# EaglesPU.net
KiCad netlist of a schematic drawn in Altium Designer
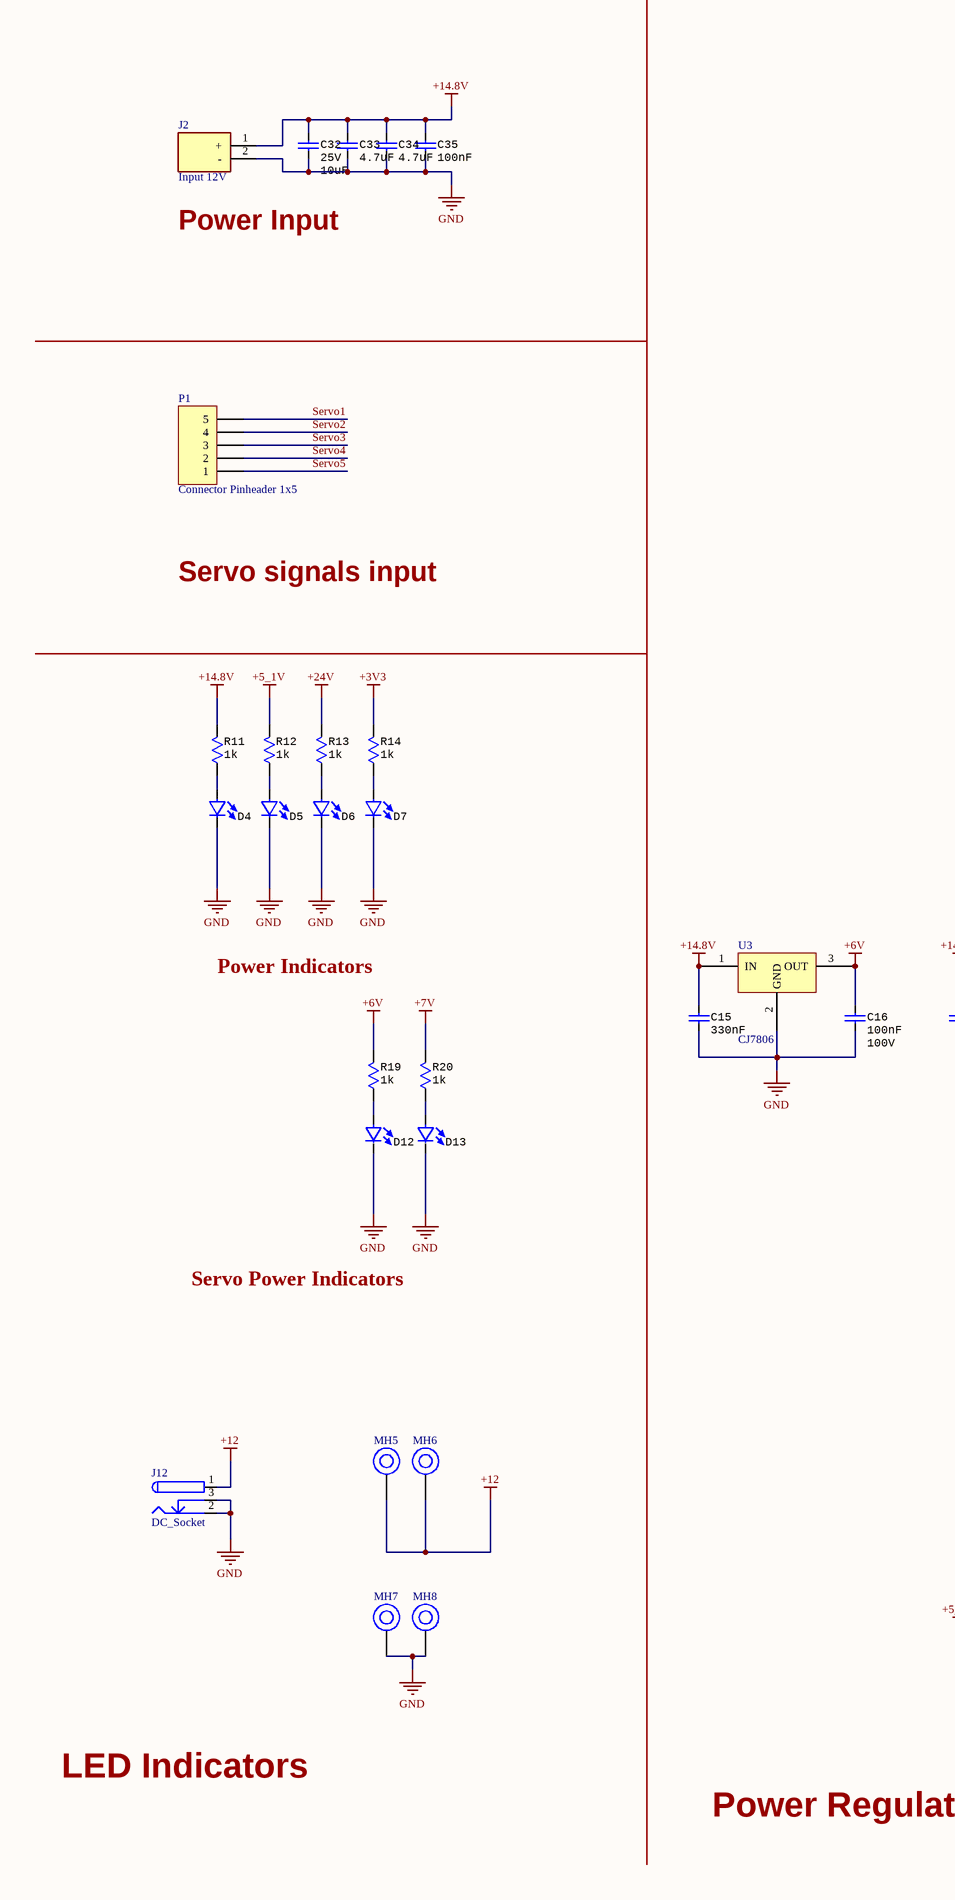
[diagram p0: EaglesPU.SchDoc, left]
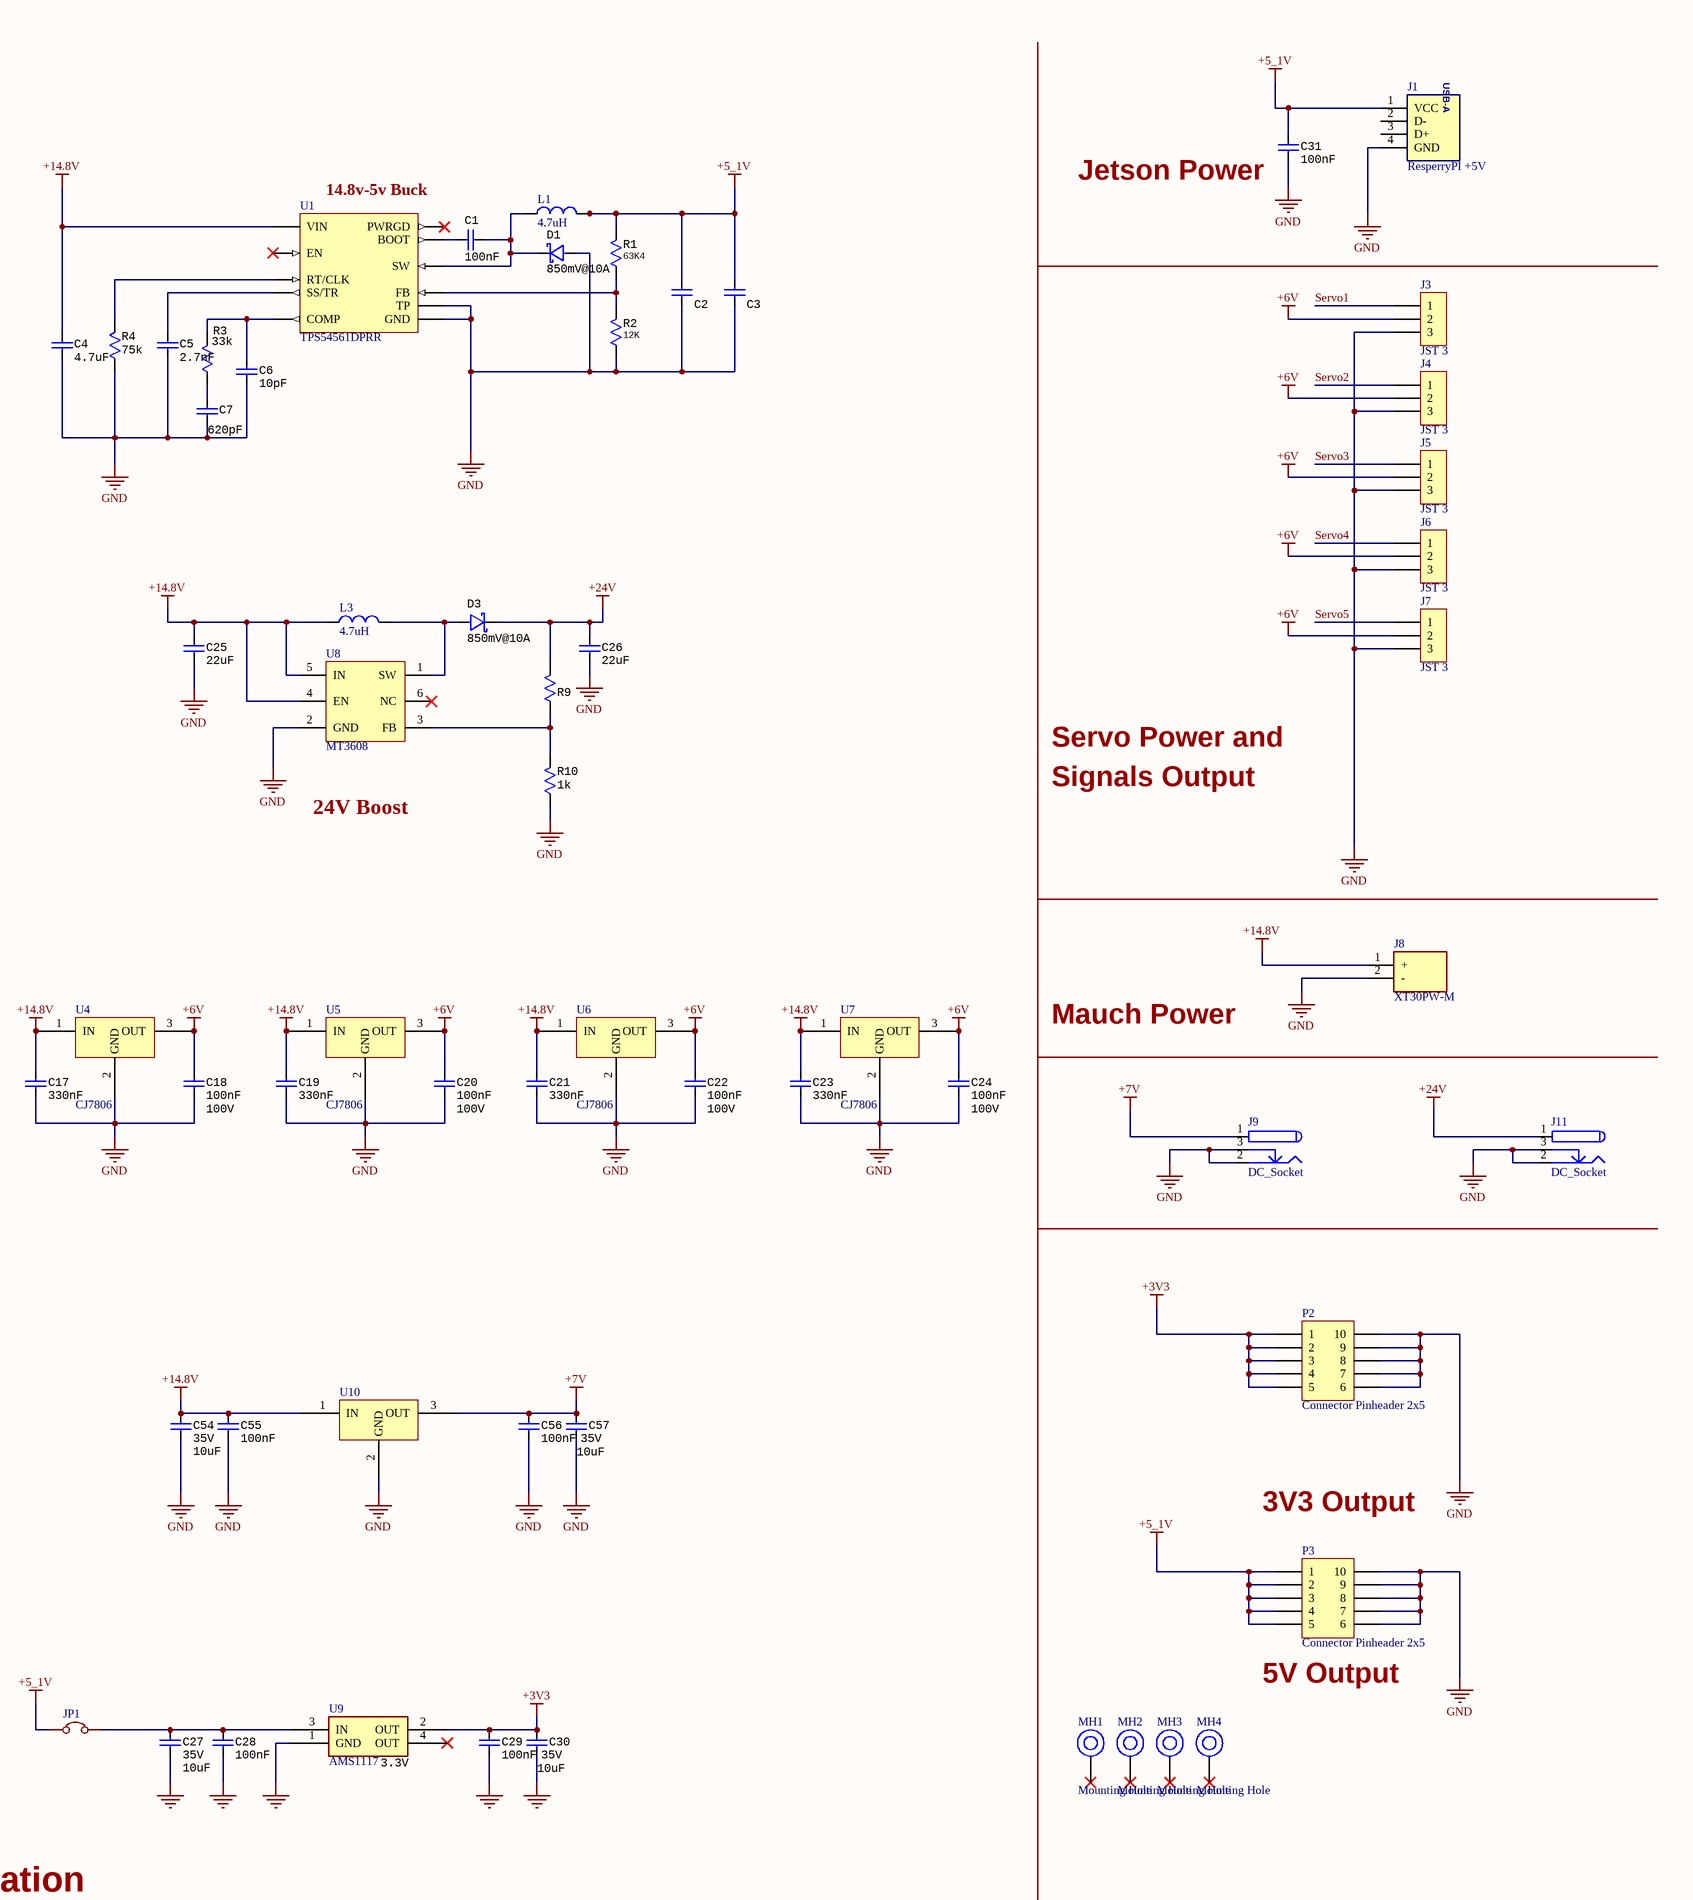
[diagram p1: EaglesPU.SchDoc, right]

(export (version "E")
  (design (tool "Eeschema 10.0.6"))
  (components
    (comp (ref "C1")
      (value "100nF")
      (footprint "CAP Ceramic SMD 0603")
      (description "0603 0.1 uF 100 V ±10% Tolerance X7R Multilayer Ceramic Capacitor")
      (fields
        (field (name "MANUFACTURER") "Yageo")
        (field (name "MANUFACTURER PART NUMBER") "CC0603KRX7R0BB104")
      )
      (libsource (lib "capacitor") (part "CAP 0603 100nF 100V"))
    )
    (comp (ref "C2")
      (value "~")
      (footprint "CAP Ceramic SMD 1206")
      (description "10V 22uF X7R ±10% 1206 Multilayer Ceramic Capacitors MLCC - SMD/SMT ROHS")
      (fields
        (field (name "MANUFACTURER") "Samsung")
        (field (name "MANUFACTURER PART NUMBER") "GRM31CR61A476ME15L")
      )
      (libsource (lib "capacitor") (part "CAP 1206 47uF 10V X5R"))
    )
    (comp (ref "C3")
      (value "~")
      (footprint "CAP Ceramic SMD 1206")
      (description "10V 22uF X7R ±10% 1206 Multilayer Ceramic Capacitors MLCC - SMD/SMT ROHS")
      (fields
        (field (name "MANUFACTURER") "Samsung")
        (field (name "MANUFACTURER PART NUMBER") "GRM31CR61A476ME15L")
      )
      (libsource (lib "capacitor") (part "CAP 1206 47uF 10V X5R"))
    )
    (comp (ref "C4")
      (value "4.7uF")
      (footprint "CAP Ceramic SMD 1206")
      (description "Cap Ceramic 4.7uF 100V X7S 10% SMD 1206 125°C Emboss T/R")
      (fields
        (field (name "MANUFACTURER PART NUMBER") "GRM31CC72A475KE11L")
        (field (name "MANUFACTURER") "Murata")
      )
      (libsource (lib "Passive") (part "CAP 1206 4.7uF 100V"))
    )
    (comp (ref "C5")
      (value "2.7nF")
      (footprint "CAP Ceramic SMD 0603")
      (description "0603 2.7 nF 50 V ±10 % Tolerance X7R SMT Multilayer Ceramic Capacitor")
      (fields
        (field (name "MANUFACTURER") "Yageo")
        (field (name "MANUFACTURER PART NUMBER") "CC0603KRX7R9BB272")
      )
      (libsource (lib "Passive") (part "CAP 0603 2.7nF 50V"))
    )
    (comp (ref "C6")
      (value "10pF")
      (footprint "CAP Ceramic SMD 0603")
      (description "Surface Mount Ceramic Multilayer Capacitor 10pF 5% C0G 50V 0603 Paper T/R")
      (fields
        (field (name "MANUFACTURER") "Yageo")
        (field (name "MANUFACTURER PART NUMBER") "CC0603JRNPO9BN100")
      )
      (libsource (lib "Passive") (part "CAP 0603 10pF 50V"))
    )
    (comp (ref "C7")
      (value "620pF")
      (footprint "CAP Ceramic SMD 0603")
      (description "Surface Mount Ceramic Multilayer Capacitor 620pF 5% C0G 50V 0603 Paper T/R")
      (fields
        (field (name "MANUFACTURER") "Yageo")
        (field (name "MANUFACTURER PART NUMBER") "CC0603JRNPO9BN621")
      )
      (libsource (lib "Passive") (part "CAP 0603 620pF 50V"))
    )
    (comp (ref "C15")
      (value "330nF")
      (footprint "CAP Ceramic SMD 0603")
      (description "Multilayer Ceramic Capacitor, 0.33 uF, 50 V, ± 10%, X7R, 0603 [1608 Metric]")
      (fields
        (field (name "MANUFACTURER") "TDK")
        (field (name "MANUFACTURER PART NUMBER") "C1608X7R1H334K080AC")
      )
      (libsource (lib "Passive") (part "CAP 0603 330nF 50V"))
    )
    (comp (ref "C16")
      (value "100nF")
      (footprint "CAP Ceramic SMD 0603")
      (description "100V 100nF X7R ±10% 0603 Multilayer Ceramic Capacitors MLCC - SMD/SMT ROHS")
      (fields
        (field (name "MANUFACTURER") "Yageo")
        (field (name "MANUFACTURER PART NUMBER") "CC0603KRX7R0BB104")
        (field (name "VOLTAGE") "100V")
      )
      (libsource (lib "capacitor") (part "CAP 0603 100nF 100V X7R 10%"))
    )
    (comp (ref "C17")
      (value "330nF")
      (footprint "CAP Ceramic SMD 0603")
      (description "Multilayer Ceramic Capacitor, 0.33 uF, 50 V, ± 10%, X7R, 0603 [1608 Metric]")
      (fields
        (field (name "MANUFACTURER") "TDK")
        (field (name "MANUFACTURER PART NUMBER") "C1608X7R1H334K080AC")
      )
      (libsource (lib "Passive") (part "CAP 0603 330nF 50V"))
    )
    (comp (ref "C18")
      (value "100nF")
      (footprint "CAP Ceramic SMD 0603")
      (description "100V 100nF X7R ±10% 0603 Multilayer Ceramic Capacitors MLCC - SMD/SMT ROHS")
      (fields
        (field (name "MANUFACTURER") "Yageo")
        (field (name "MANUFACTURER PART NUMBER") "CC0603KRX7R0BB104")
        (field (name "VOLTAGE") "100V")
      )
      (libsource (lib "capacitor") (part "CAP 0603 100nF 100V X7R 10%"))
    )
    (comp (ref "C19")
      (value "330nF")
      (footprint "CAP Ceramic SMD 0603")
      (description "Multilayer Ceramic Capacitor, 0.33 uF, 50 V, ± 10%, X7R, 0603 [1608 Metric]")
      (fields
        (field (name "MANUFACTURER") "TDK")
        (field (name "MANUFACTURER PART NUMBER") "C1608X7R1H334K080AC")
      )
      (libsource (lib "Passive") (part "CAP 0603 330nF 50V"))
    )
    (comp (ref "C20")
      (value "100nF")
      (footprint "CAP Ceramic SMD 0603")
      (description "100V 100nF X7R ±10% 0603 Multilayer Ceramic Capacitors MLCC - SMD/SMT ROHS")
      (fields
        (field (name "MANUFACTURER") "Yageo")
        (field (name "MANUFACTURER PART NUMBER") "CC0603KRX7R0BB104")
        (field (name "VOLTAGE") "100V")
      )
      (libsource (lib "capacitor") (part "CAP 0603 100nF 100V X7R 10%"))
    )
    (comp (ref "C21")
      (value "330nF")
      (footprint "CAP Ceramic SMD 0603")
      (description "Multilayer Ceramic Capacitor, 0.33 uF, 50 V, ± 10%, X7R, 0603 [1608 Metric]")
      (fields
        (field (name "MANUFACTURER") "TDK")
        (field (name "MANUFACTURER PART NUMBER") "C1608X7R1H334K080AC")
      )
      (libsource (lib "Passive") (part "CAP 0603 330nF 50V"))
    )
    (comp (ref "C22")
      (value "100nF")
      (footprint "CAP Ceramic SMD 0603")
      (description "100V 100nF X7R ±10% 0603 Multilayer Ceramic Capacitors MLCC - SMD/SMT ROHS")
      (fields
        (field (name "MANUFACTURER") "Yageo")
        (field (name "MANUFACTURER PART NUMBER") "CC0603KRX7R0BB104")
        (field (name "VOLTAGE") "100V")
      )
      (libsource (lib "capacitor") (part "CAP 0603 100nF 100V X7R 10%"))
    )
    (comp (ref "C23")
      (value "330nF")
      (footprint "CAP Ceramic SMD 0603")
      (description "Multilayer Ceramic Capacitor, 0.33 uF, 50 V, ± 10%, X7R, 0603 [1608 Metric]")
      (fields
        (field (name "MANUFACTURER") "TDK")
        (field (name "MANUFACTURER PART NUMBER") "C1608X7R1H334K080AC")
      )
      (libsource (lib "Passive") (part "CAP 0603 330nF 50V"))
    )
    (comp (ref "C24")
      (value "100nF")
      (footprint "CAP Ceramic SMD 0603")
      (description "100V 100nF X7R ±10% 0603 Multilayer Ceramic Capacitors MLCC - SMD/SMT ROHS")
      (fields
        (field (name "MANUFACTURER") "Yageo")
        (field (name "MANUFACTURER PART NUMBER") "CC0603KRX7R0BB104")
        (field (name "VOLTAGE") "100V")
      )
      (libsource (lib "capacitor") (part "CAP 0603 100nF 100V X7R 10%"))
    )
    (comp (ref "C25")
      (value "22uF")
      (footprint "CAP Ceramic SMD 0603")
      (description "6.3V 22uF X5R ±20% 0603 Multilayer Ceramic Capacitors MLCC - SMD/SMT ROHS")
      (fields
        (field (name "MANUFACTURER") "YAGEO")
        (field (name "VOLTAGE") "6.3V")
        (field (name "CAPACITANCE") "22uF")
      )
      (libsource (lib "Passive") (part "CAP 0603 22uF 6.3V"))
    )
    (comp (ref "C26")
      (value "22uF")
      (footprint "CAP Ceramic SMD 0603")
      (description "6.3V 22uF X5R ±20% 0603 Multilayer Ceramic Capacitors MLCC - SMD/SMT ROHS")
      (fields
        (field (name "MANUFACTURER") "YAGEO")
        (field (name "VOLTAGE") "6.3V")
        (field (name "CAPACITANCE") "22uF")
      )
      (libsource (lib "Passive") (part "CAP 0603 22uF 6.3V"))
    )
    (comp (ref "C27")
      (value "10uF")
      (footprint "CAP Ceramic SMD 0603")
      (description "Cap Ceramic 10uF 35V X5R 20% Pad SMD 0603 85C T/R")
      (fields
        (field (name "MANUFACTURER") "Murata")
        (field (name "MANUFACTURER PART NUMBER") "GRM188R6YA106MA73D")
        (field (name "VOLTAGE") "35V")
      )
      (libsource (lib "Passive") (part "CAP 0603 10uF 35V"))
    )
    (comp (ref "C28")
      (value "100nF")
      (footprint "CAP Ceramic SMD 0603")
      (description "0603 0.1 uF 100 V ±10% Tolerance X7R Multilayer Ceramic Capacitor")
      (fields
        (field (name "MANUFACTURER") "Yageo")
        (field (name "MANUFACTURER PART NUMBER") "AC0603KRX7R0BB104")
      )
      (libsource (lib "capacitor") (part "CAP 0603 100nF 100V"))
    )
    (comp (ref "C29")
      (value "100nF")
      (footprint "CAP Ceramic SMD 0603")
      (description "0603 0.1 uF 100 V ±10% Tolerance X7R Multilayer Ceramic Capacitor")
      (fields
        (field (name "MANUFACTURER") "Yageo")
        (field (name "MANUFACTURER PART NUMBER") "AC0603KRX7R0BB104")
      )
      (libsource (lib "capacitor") (part "CAP 0603 100nF 100V"))
    )
    (comp (ref "C30")
      (value "10uF")
      (footprint "CAP Ceramic SMD 0603")
      (description "Cap Ceramic 10uF 35V X5R 20% Pad SMD 0603 85C T/R")
      (fields
        (field (name "MANUFACTURER") "Murata")
        (field (name "MANUFACTURER PART NUMBER") "GRM188R6YA106MA73D")
        (field (name "VOLTAGE") "35V")
      )
      (libsource (lib "Passive") (part "CAP 0603 10uF 35V"))
    )
    (comp (ref "C31")
      (value "100nF")
      (footprint "CAP Ceramic SMD 0603")
      (description "0603 0.1 uF 100 V ±10% Tolerance X7R Multilayer Ceramic Capacitor")
      (fields
        (field (name "MANUFACTURER") "Yageo")
        (field (name "MANUFACTURER PART NUMBER") "CC0603KRX7R0BB104")
      )
      (libsource (lib "capacitor") (part "CAP 0603 100nF 100V"))
    )
    (comp (ref "C32")
      (value "10uF")
      (footprint "CAP Ceramic SMD 1206")
      (description "25V 10uF X7R ±10% 1206 Multilayer Ceramic Capacitors MLCC - SMD/SMT ROHS")
      (fields
        (field (name "MANUFACTURER") "Samsung Electro-Mechanics")
        (field (name "MANUFACTURER PART NUMBER") "CL31B106KAHNNNE")
        (field (name "VOLTAGE") "25V")
      )
      (libsource (lib "capacitor") (part "CAP 1206 10uF 25V X7R 10%"))
    )
    (comp (ref "C33")
      (value "4.7uF")
      (footprint "CAP Ceramic SMD 1206")
      (description "Cap Ceramic 4.7uF 100V X7S 10% SMD 1206 125°C Emboss T/R")
      (fields
        (field (name "MANUFACTURER PART NUMBER") "GRM31CC72A475KE11L")
        (field (name "MANUFACTURER") "Murata")
      )
      (libsource (lib "Passive") (part "CAP 1206 4.7uF 100V"))
    )
    (comp (ref "C34")
      (value "4.7uF")
      (footprint "CAP Ceramic SMD 1206")
      (description "Cap Ceramic 4.7uF 100V X7S 10% SMD 1206 125°C Emboss T/R")
      (fields
        (field (name "MANUFACTURER PART NUMBER") "GRM31CC72A475KE11L")
        (field (name "MANUFACTURER") "Murata")
      )
      (libsource (lib "Passive") (part "CAP 1206 4.7uF 100V"))
    )
    (comp (ref "C35")
      (value "100nF")
      (footprint "CAP Ceramic SMD 0603")
      (description "0603 0.1 uF 100 V ±10% Tolerance X7R Multilayer Ceramic Capacitor")
      (fields
        (field (name "MANUFACTURER") "Yageo")
        (field (name "MANUFACTURER PART NUMBER") "CC0603KRX7R0BB104")
      )
      (libsource (lib "capacitor") (part "CAP 0603 100nF 100V"))
    )
    (comp (ref "C54")
      (value "10uF")
      (footprint "CAP Ceramic SMD 0603")
      (description "Cap Ceramic 10uF 35V X5R 20% Pad SMD 0603 85C T/R")
      (fields
        (field (name "MANUFACTURER") "Murata")
        (field (name "MANUFACTURER PART NUMBER") "GRM188R6YA106MA73D")
        (field (name "VOLTAGE") "35V")
      )
      (libsource (lib "Passive") (part "CAP 0603 10uF 35V"))
    )
    (comp (ref "C55")
      (value "100nF")
      (footprint "CAP Ceramic SMD 0603")
      (description "0603 0.1 uF 100 V ±10% Tolerance X7R Multilayer Ceramic Capacitor")
      (fields
        (field (name "MANUFACTURER") "Yageo")
        (field (name "MANUFACTURER PART NUMBER") "AC0603KRX7R0BB104")
      )
      (libsource (lib "capacitor") (part "CAP 0603 100nF 100V"))
    )
    (comp (ref "C56")
      (value "100nF")
      (footprint "CAP Ceramic SMD 0603")
      (description "0603 0.1 uF 100 V ±10% Tolerance X7R Multilayer Ceramic Capacitor")
      (fields
        (field (name "MANUFACTURER") "Yageo")
        (field (name "MANUFACTURER PART NUMBER") "AC0603KRX7R0BB104")
      )
      (libsource (lib "capacitor") (part "CAP 0603 100nF 100V"))
    )
    (comp (ref "C57")
      (value "10uF")
      (footprint "CAP Ceramic SMD 0603")
      (description "Cap Ceramic 10uF 35V X5R 20% Pad SMD 0603 85C T/R")
      (fields
        (field (name "MANUFACTURER") "Murata")
        (field (name "MANUFACTURER PART NUMBER") "GRM188R6YA106MA73D")
        (field (name "VOLTAGE") "35V")
      )
      (libsource (lib "Passive") (part "CAP 0603 10uF 35V"))
    )
    (comp (ref "D1")
      (value "850mV@10A")
      (footprint "TO-277")
      (description "100V 750mV@10A 10A TO-277 Schottky Barrier Diodes (SBD) ROHS")
      (fields
        (field (name "MANUFACTURER") "MDD（Microdiode Electronics）")
        (field (name "MANUFACTURER PART NUMBER") "SB10100L")
      )
      (libsource (lib "Diode") (part "Schottky 100V 750mV@10A"))
    )
    (comp (ref "D3")
      (value "850mV@10A")
      (footprint "TO-277")
      (description "100V 750mV@10A 10A TO-277 Schottky Barrier Diodes (SBD) ROHS")
      (fields
        (field (name "MANUFACTURER") "MDD（Microdiode Electronics）")
        (field (name "MANUFACTURER PART NUMBER") "SB10100L")
      )
      (libsource (lib "Diode") (part "Schottky 100V 750mV@10A"))
    )
    (comp (ref "D4")
      (value "~")
      (footprint "LED SMD 0805G")
      (description "emerald 0805 Light Emitting Diodes (LED) ROHS")
      (fields
        (field (name "MANUFACTURER") "FOSHAN Nationstar Optoelectronics")
        (field (name "MANUFACTURER PART NUMBER") "NCD0805G1")
      )
      (libsource (lib "diode") (part "LED 0805 Emerald"))
    )
    (comp (ref "D5")
      (value "~")
      (footprint "LED SMD 0805G")
      (description "emerald 0805 Light Emitting Diodes (LED) ROHS")
      (fields
        (field (name "MANUFACTURER") "FOSHAN Nationstar Optoelectronics")
        (field (name "MANUFACTURER PART NUMBER") "NCD0805G1")
      )
      (libsource (lib "diode") (part "LED 0805 Emerald"))
    )
    (comp (ref "D6")
      (value "~")
      (footprint "LED SMD 0805G")
      (description "emerald 0805 Light Emitting Diodes (LED) ROHS")
      (fields
        (field (name "MANUFACTURER") "FOSHAN Nationstar Optoelectronics")
        (field (name "MANUFACTURER PART NUMBER") "NCD0805G1")
      )
      (libsource (lib "diode") (part "LED 0805 Emerald"))
    )
    (comp (ref "D7")
      (value "~")
      (footprint "LED SMD 0805G")
      (description "emerald 0805 Light Emitting Diodes (LED) ROHS")
      (fields
        (field (name "MANUFACTURER") "FOSHAN Nationstar Optoelectronics")
        (field (name "MANUFACTURER PART NUMBER") "NCD0805G1")
      )
      (libsource (lib "diode") (part "LED 0805 Emerald"))
    )
    (comp (ref "D12")
      (value "~")
      (footprint "LED SMD 0805G")
      (description "emerald 0805 Light Emitting Diodes (LED) ROHS")
      (fields
        (field (name "MANUFACTURER") "FOSHAN Nationstar Optoelectronics")
        (field (name "MANUFACTURER PART NUMBER") "NCD0805G1")
      )
      (libsource (lib "diode") (part "LED 0805 Emerald"))
    )
    (comp (ref "D13")
      (value "~")
      (footprint "LED SMD 0805G")
      (description "emerald 0805 Light Emitting Diodes (LED) ROHS")
      (fields
        (field (name "MANUFACTURER") "FOSHAN Nationstar Optoelectronics")
        (field (name "MANUFACTURER PART NUMBER") "NCD0805G1")
      )
      (libsource (lib "diode") (part "LED 0805 Emerald"))
    )
    (comp (ref "J1")
      (value "ResperryPI +5V")
      (footprint "USB-A/S_A")
      (libsource (lib "USB connectors") (part "Connector_USB-A"))
    )
    (comp (ref "J2")
      (value "Input 12V")
      (footprint "XT60PW-M")
      (description "Power Connectors ROHS")
      (fields
        (field (name "MANUFACTURER") "Changzhou Amass Elec")
        (field (name "MANUFACTURERPARTNUMBER") "XT60PW-M")
      )
      (libsource (lib "Power connectors") (part "XT60PW-M"))
    )
    (comp (ref "J3")
      (value "JST 3")
      (footprint "VH3.96-3AW")
      (description "MaleHeader 3x1")
      (libsource (lib "Signal connectors") (part "JST 3"))
    )
    (comp (ref "J4")
      (value "JST 3")
      (footprint "VH3.96-3AW")
      (description "MaleHeader 3x1")
      (libsource (lib "Signal connectors") (part "JST 3"))
    )
    (comp (ref "J5")
      (value "JST 3")
      (footprint "VH3.96-3AW")
      (description "MaleHeader 3x1")
      (libsource (lib "Signal connectors") (part "JST 3"))
    )
    (comp (ref "J6")
      (value "JST 3")
      (footprint "VH3.96-3AW")
      (description "MaleHeader 3x1")
      (libsource (lib "Signal connectors") (part "JST 3"))
    )
    (comp (ref "J7")
      (value "JST 3")
      (footprint "VH3.96-3AW")
      (description "MaleHeader 3x1")
      (libsource (lib "Signal connectors") (part "JST 3"))
    )
    (comp (ref "J8")
      (value "XT30PW-M")
      (footprint "AMASS_XT30PW-F")
      (description "Power Connectors ROHS")
      (fields (field (name "MANUFACTURER") "Changzhou Amass Elec"))
      (libsource (lib "Power connectors") (part "XT30PW-M"))
    )
    (comp (ref "J9")
      (value "DC_Socket")
      (footprint "DC-002")
      (description "CIRCULAR DC POWER CONNECTOR\r\nRated Current: 7.5A\r\nRated Volatage: 20VDC")
      (libsource (lib "Power connectors") (part "DC_Socket"))
    )
    (comp (ref "J11")
      (value "DC_Socket")
      (footprint "DC-002")
      (description "CIRCULAR DC POWER CONNECTOR\r\nRated Current: 7.5A\r\nRated Volatage: 20VDC")
      (libsource (lib "Power connectors") (part "DC_Socket"))
    )
    (comp (ref "J12")
      (value "DC_Socket")
      (footprint "DC-002")
      (description "CIRCULAR DC POWER CONNECTOR\r\nRated Current: 7.5A\r\nRated Volatage: 20VDC")
      (libsource (lib "") (part "DC_Socket_1"))
    )
    (comp (ref "JP1")
      (value "Jumper TH 2 NC")
      (footprint "Jumber TH 2 NC")
      (description "Normally closed jumper")
      (fields (field (name "MANUFACTURER") "XFCN") (field (name "MANUFACTURER PART NUMBER") "PZ254V-11-02P"))
      (libsource (lib "Bypass, Testpoint and Holes") (part "Jumper TH 2 NC"))
    )
    (comp (ref "L1")
      (value "4.7uH")
      (footprint "XLS1040")
      (description "9A 4.7uH ±20% 17mΩ 15A SMD,11.5x10x3.8mm Power Inductors ROHS")
      (fields
        (field (name "MANUFACTURER") "Cjiang")
        (field (name "MANUFACTURER PART NUMBER") "FXL1040-4R7-M")
      )
      (libsource (lib "Passive") (part "IND 0403 4.7uH 20%"))
    )
    (comp (ref "L3")
      (value "4.7uH")
      (footprint "XLS1040")
      (description "9A 4.7uH ±20% 17mΩ 15A SMD,11.5x10x3.8mm Power Inductors ROHS")
      (fields
        (field (name "MANUFACTURER") "Cjiang")
        (field (name "MANUFACTURER PART NUMBER") "FXL1040-4R7-M")
      )
      (libsource (lib "Passive") (part "IND 0403 4.7uH 20%"))
    )
    (comp (ref "MH1")
      (value "Mounting Hole")
      (footprint "Connector Mounting hole TH 3mm")
      (libsource (lib "Bypass, Testpoint and Holes") (part "Mounting Hole"))
    )
    (comp (ref "MH2")
      (value "Mounting Hole")
      (footprint "Connector Mounting hole TH 3mm")
      (libsource (lib "Bypass, Testpoint and Holes") (part "Mounting Hole"))
    )
    (comp (ref "MH3")
      (value "Mounting Hole")
      (footprint "Connector Mounting hole TH 3mm")
      (libsource (lib "Bypass, Testpoint and Holes") (part "Mounting Hole"))
    )
    (comp (ref "MH4")
      (value "Mounting Hole")
      (footprint "Connector Mounting hole TH 3mm")
      (libsource (lib "Bypass, Testpoint and Holes") (part "Mounting Hole"))
    )
    (comp (ref "MH5")
      (value "Mounting Hole")
      (footprint "Connector Mounting hole TH 1mm SOLID")
      (libsource (lib "Bypass, Testpoint and Holes") (part "Mounting Hole"))
    )
    (comp (ref "MH6")
      (value "Mounting Hole")
      (footprint "Connector Mounting hole TH 1mm SOLID")
      (libsource (lib "Bypass, Testpoint and Holes") (part "Mounting Hole"))
    )
    (comp (ref "MH7")
      (value "Mounting Hole")
      (footprint "Connector Mounting hole TH 1mm SOLID")
      (libsource (lib "Bypass, Testpoint and Holes") (part "Mounting Hole"))
    )
    (comp (ref "MH8")
      (value "Mounting Hole")
      (footprint "Connector Mounting hole TH 1mm SOLID")
      (libsource (lib "Bypass, Testpoint and Holes") (part "Mounting Hole"))
    )
    (comp (ref "P1")
      (value "Connector Pinheader 1x5")
      (footprint "Header 2.54X5")
      (description "Header_5x1")
      (libsource (lib "Signal connectors") (part "Connector Pinheader 1x5"))
    )
    (comp (ref "P2")
      (value "Connector Pinheader 2x5")
      (footprint "Header 2.54_2X5")
      (description "Header_2X5")
      (libsource (lib "Signal connectors") (part "Connector Pinheader 2x5"))
    )
    (comp (ref "P3")
      (value "Connector Pinheader 2x5")
      (footprint "Header 2.54_2X5")
      (description "Header_2X5")
      (libsource (lib "Signal connectors") (part "Connector Pinheader 2x5"))
    )
    (comp (ref "R1")
      (value "63K4")
      (footprint "RES SMD 0603")
      (fields
        (field (name "MANUFACTURER") "Yageo")
        (field (name "MANUFACTURER PART NUMBER") "AC0603FR-0763K4L")
        (field (name "TOLERANCE") "1%")
      )
      (libsource (lib "Passive") (part "RES 0603 63K4 1%"))
    )
    (comp (ref "R2")
      (value "12K")
      (footprint "RES SMD 0603")
      (fields
        (field (name "MANUFACTURER") "Yageo")
        (field (name "MANUFACTURER PART NUMBER") "RC0603FR-0712KL")
        (field (name "TOLERANCE") "1%")
      )
      (libsource (lib "Passive") (part "RES 0603 12K 1%"))
    )
    (comp (ref "R3")
      (value "33k")
      (footprint "RES SMD 0603")
      (fields
        (field (name "MANUFACTURER") "Uniroyal")
        (field (name "MANUFACTURER PART NUMBER") "0603WAF3902T5E")
      )
      (libsource (lib "Passive") (part "RES 0603 39k 1%"))
    )
    (comp (ref "R4")
      (value "75k")
      (footprint "RES SMD 0603")
      (description "Res Thick Film 0603 75K Ohm 1% 0.1W(1/10W) ±100ppm/C Pad SMD Automotive T/R")
      (fields
        (field (name "MANUFACTURER") "Panasonic")
        (field (name "MANUFACTURER PART NUMBER") "ERJ3RBD7502V")
      )
      (libsource (lib "Passive") (part "RES 0603 75k 1%"))
    )
    (comp (ref "R9")
      (value "~")
      (footprint "RES SMD 0603")
      (fields
        (field (name "MANUFACTURER") "Uniroyal")
        (field (name "MANUFACTURER PART NUMBER") "0603WAF3902T5E")
      )
      (libsource (lib "Passive") (part "RES 0603 39k 1%"))
    )
    (comp (ref "R10")
      (value "1k")
      (footprint "RES SMD 0603")
      (description "Res Thick Film 0603 1K Ohm 1% 1/10W ±100ppm/°C Molded SMD Punched Carrier T/R")
      (fields
        (field (name "MANUFACTURER") "Panasonic")
        (field (name "MANUFACTURER PART NUMBER") "ERJ3EKF1001V")
      )
      (libsource (lib "Passive") (part "RES 0603 1k 1%"))
    )
    (comp (ref "R11")
      (value "1k")
      (footprint "RES SMD 0603")
      (description "Res Thick Film 0603 1K Ohm 1% 1/10W ±100ppm/°C Molded SMD Punched Carrier T/R")
      (fields
        (field (name "MANUFACTURER") "Panasonic")
        (field (name "MANUFACTURER PART NUMBER") "ERJ3EKF1001V")
      )
      (libsource (lib "Passive") (part "RES 0603 1k 1%"))
    )
    (comp (ref "R12")
      (value "1k")
      (footprint "RES SMD 0603")
      (description "Res Thick Film 0603 1K Ohm 1% 1/10W ±100ppm/°C Molded SMD Punched Carrier T/R")
      (fields
        (field (name "MANUFACTURER") "Panasonic")
        (field (name "MANUFACTURER PART NUMBER") "ERJ3EKF1001V")
      )
      (libsource (lib "Passive") (part "RES 0603 1k 1%"))
    )
    (comp (ref "R13")
      (value "1k")
      (footprint "RES SMD 0603")
      (description "Res Thick Film 0603 1K Ohm 1% 1/10W ±100ppm/°C Molded SMD Punched Carrier T/R")
      (fields
        (field (name "MANUFACTURER") "Panasonic")
        (field (name "MANUFACTURER PART NUMBER") "ERJ3EKF1001V")
      )
      (libsource (lib "Passive") (part "RES 0603 1k 1%"))
    )
    (comp (ref "R14")
      (value "1k")
      (footprint "RES SMD 0603")
      (description "Res Thick Film 0603 1K Ohm 1% 1/10W ±100ppm/°C Molded SMD Punched Carrier T/R")
      (fields
        (field (name "MANUFACTURER") "Panasonic")
        (field (name "MANUFACTURER PART NUMBER") "ERJ3EKF1001V")
      )
      (libsource (lib "Passive") (part "RES 0603 1k 1%"))
    )
    (comp (ref "R19")
      (value "1k")
      (footprint "RES SMD 0603")
      (description "Res Thick Film 0603 1K Ohm 1% 1/10W ±100ppm/°C Molded SMD Punched Carrier T/R")
      (fields
        (field (name "MANUFACTURER") "Panasonic")
        (field (name "MANUFACTURER PART NUMBER") "ERJ3EKF1001V")
      )
      (libsource (lib "Passive") (part "RES 0603 1k 1%"))
    )
    (comp (ref "R20")
      (value "1k")
      (footprint "RES SMD 0603")
      (description "Res Thick Film 0603 1K Ohm 1% 1/10W ±100ppm/°C Molded SMD Punched Carrier T/R")
      (fields
        (field (name "MANUFACTURER") "Panasonic")
        (field (name "MANUFACTURER PART NUMBER") "ERJ3EKF1001V")
      )
      (libsource (lib "Passive") (part "RES 0603 1k 1%"))
    )
    (comp (ref "U1")
      (value "TPS54561DPRR")
      (footprint "TPS54561DPRR")
      (description "4.5V to 60V Input 5A Step-Down DC-DC Converter With Soft-Start and Eco-mode 10-WSON -40 to 125")
      (fields (field (name "MANUFACTURER") "Texas Instruments"))
      (libsource (lib "PMIC") (part "TPS54561DPRR"))
    )
    (comp (ref "U3")
      (value "CJ7806")
      (footprint "REGULATOR TO-252(4R)-2L")
      (fields (field (name "MANUFACTURER") "JIANGSU CHANGJIANG ELECTRONICS TECHNOLOGY CO., LTD"))
      (libsource (lib "PMIC") (part "CJ7806"))
    )
    (comp (ref "U4")
      (value "CJ7806")
      (footprint "REGULATOR TO-252(4R)-2L")
      (fields (field (name "MANUFACTURER") "JIANGSU CHANGJIANG ELECTRONICS TECHNOLOGY CO., LTD"))
      (libsource (lib "PMIC") (part "CJ7806"))
    )
    (comp (ref "U5")
      (value "CJ7806")
      (footprint "REGULATOR TO-252(4R)-2L")
      (fields (field (name "MANUFACTURER") "JIANGSU CHANGJIANG ELECTRONICS TECHNOLOGY CO., LTD"))
      (libsource (lib "PMIC") (part "CJ7806"))
    )
    (comp (ref "U6")
      (value "CJ7806")
      (footprint "REGULATOR TO-252(4R)-2L")
      (fields (field (name "MANUFACTURER") "JIANGSU CHANGJIANG ELECTRONICS TECHNOLOGY CO., LTD"))
      (libsource (lib "PMIC") (part "CJ7806"))
    )
    (comp (ref "U7")
      (value "CJ7806")
      (footprint "REGULATOR TO-252(4R)-2L")
      (fields (field (name "MANUFACTURER") "JIANGSU CHANGJIANG ELECTRONICS TECHNOLOGY CO., LTD"))
      (libsource (lib "PMIC") (part "CJ7806"))
    )
    (comp (ref "U8")
      (value "MT3608")
      (footprint "MT3608")
      (description "boost converterType 28V 2V~24V SOT-23-6 DC-DC Converters ROHS")
      (fields (field (name "MANUFACTURER") "XI'AN Aerosemi Tech"))
      (libsource (lib "PMIC") (part "MT3608"))
    )
    (comp (ref "U9")
      (value "AMS1117")
      (footprint "Linear reagulator SMD AMS1117 - duplicate")
      (fields
        (field (name "MANUFACTURER") "Advanced Monolithic Systems")
        (field (name "VOLTAGE OUTPUT") "3.3V")
      )
      (libsource (lib "Linear regulator") (part "AMS1117"))
    )
    (comp (ref "U10")
      (value "BA7807FP-E2")
      (footprint "BA7807FP-E2")
      (description "1A 69dB@(120Hz) Fixed 7V Positive electrode 22V TO-252-3 Linear Voltage Regulators (LDO) ROHS")
      (fields (field (name "MANUFACTURER") "ROHM Semicon"))
      (libsource (lib "PMIC") (part "BA7807FP-E2"))
    )
  )
  (nets
    (net (code "1") (name "+3V3") (class "Default")
      (node (ref "C29") (pin "1") (pinfunction "1_1") (pintype "passive"))
      (node (ref "C30") (pin "1") (pinfunction "1_1") (pintype "passive"))
      (node (ref "P2") (pin "1") (pinfunction "1_1") (pintype "power_in"))
      (node (ref "P2") (pin "2") (pinfunction "2_2") (pintype "power_in"))
      (node (ref "P2") (pin "3") (pinfunction "3_3") (pintype "power_in"))
      (node (ref "P2") (pin "4") (pinfunction "4_4") (pintype "power_in"))
      (node (ref "P2") (pin "5") (pinfunction "5_5") (pintype "power_in"))
      (node (ref "R14") (pin "2") (pinfunction "2_2") (pintype "passive"))
      (node (ref "U9") (pin "2") (pinfunction "OUT_2") (pintype "passive"))
    )
    (net (code "2") (name "+5_1V") (class "Default")
      (node (ref "C2") (pin "1") (pinfunction "1_1") (pintype "passive"))
      (node (ref "C3") (pin "1") (pinfunction "1_1") (pintype "passive"))
      (node (ref "C31") (pin "1") (pinfunction "1_1") (pintype "passive"))
      (node (ref "J1") (pin "1") (pinfunction "VCC_1") (pintype "passive"))
      (node (ref "JP1") (pin "1") (pinfunction "1_1") (pintype "passive"))
      (node (ref "L1") (pin "1") (pinfunction "1_1") (pintype "passive"))
      (node (ref "P3") (pin "1") (pinfunction "1_1") (pintype "power_in"))
      (node (ref "P3") (pin "2") (pinfunction "2_2") (pintype "power_in"))
      (node (ref "P3") (pin "3") (pinfunction "3_3") (pintype "power_in"))
      (node (ref "P3") (pin "4") (pinfunction "4_4") (pintype "power_in"))
      (node (ref "P3") (pin "5") (pinfunction "5_5") (pintype "power_in"))
      (node (ref "R1") (pin "2") (pinfunction "2_2") (pintype "passive"))
      (node (ref "R12") (pin "2") (pinfunction "2_2") (pintype "passive"))
    )
    (net (code "3") (name "+6V") (class "Default")
      (node (ref "C16") (pin "1") (pinfunction "1_1") (pintype "passive"))
      (node (ref "C18") (pin "1") (pinfunction "1_1") (pintype "passive"))
      (node (ref "C20") (pin "1") (pinfunction "1_1") (pintype "passive"))
      (node (ref "C22") (pin "1") (pinfunction "1_1") (pintype "passive"))
      (node (ref "C24") (pin "1") (pinfunction "1_1") (pintype "passive"))
      (node (ref "J3") (pin "2") (pinfunction "2_2") (pintype "passive"))
      (node (ref "J4") (pin "2") (pinfunction "2_2") (pintype "passive"))
      (node (ref "J5") (pin "2") (pinfunction "2_2") (pintype "passive"))
      (node (ref "J6") (pin "2") (pinfunction "2_2") (pintype "passive"))
      (node (ref "J7") (pin "2") (pinfunction "2_2") (pintype "passive"))
      (node (ref "R19") (pin "2") (pinfunction "2_2") (pintype "passive"))
      (node (ref "U3") (pin "3") (pinfunction "OUT_3") (pintype "passive"))
      (node (ref "U4") (pin "3") (pinfunction "OUT_3") (pintype "passive"))
      (node (ref "U5") (pin "3") (pinfunction "OUT_3") (pintype "passive"))
      (node (ref "U6") (pin "3") (pinfunction "OUT_3") (pintype "passive"))
      (node (ref "U7") (pin "3") (pinfunction "OUT_3") (pintype "passive"))
    )
    (net (code "4") (name "+7V") (class "Default")
      (node (ref "C56") (pin "1") (pinfunction "1_1") (pintype "passive"))
      (node (ref "C57") (pin "1") (pinfunction "1_1") (pintype "passive"))
      (node (ref "J9") (pin "1") (pinfunction "1_1") (pintype "power_in"))
      (node (ref "R20") (pin "2") (pinfunction "2_2") (pintype "passive"))
      (node (ref "U10") (pin "3") (pinfunction "OUT_3") (pintype "passive"))
    )
    (net (code "5") (name "+12") (class "Default")
      (node (ref "J12") (pin "1") (pinfunction "1_1") (pintype "power_in"))
      (node (ref "MH5") (pin "1") (pinfunction "1_1") (pintype "passive"))
      (node (ref "MH6") (pin "1") (pinfunction "1_1") (pintype "passive"))
    )
    (net (code "6") (name "+14.8V") (class "Default")
      (node (ref "C15") (pin "1") (pinfunction "1_1") (pintype "passive"))
      (node (ref "C17") (pin "1") (pinfunction "1_1") (pintype "passive"))
      (node (ref "C19") (pin "1") (pinfunction "1_1") (pintype "passive"))
      (node (ref "C21") (pin "1") (pinfunction "1_1") (pintype "passive"))
      (node (ref "C23") (pin "1") (pinfunction "1_1") (pintype "passive"))
      (node (ref "C25") (pin "1") (pinfunction "1_1") (pintype "passive"))
      (node (ref "C32") (pin "1") (pinfunction "1_1") (pintype "passive"))
      (node (ref "C33") (pin "1") (pinfunction "1_1") (pintype "passive"))
      (node (ref "C34") (pin "1") (pinfunction "1_1") (pintype "passive"))
      (node (ref "C35") (pin "1") (pinfunction "1_1") (pintype "passive"))
      (node (ref "C4") (pin "1") (pinfunction "1_1") (pintype "passive"))
      (node (ref "C54") (pin "1") (pinfunction "1_1") (pintype "passive"))
      (node (ref "C55") (pin "1") (pinfunction "1_1") (pintype "passive"))
      (node (ref "J2") (pin "1") (pinfunction "+_1") (pintype "passive"))
      (node (ref "J8") (pin "1") (pinfunction "+_1") (pintype "passive"))
      (node (ref "L3") (pin "2") (pinfunction "2_2") (pintype "passive"))
      (node (ref "R11") (pin "2") (pinfunction "2_2") (pintype "passive"))
      (node (ref "U1") (pin "2") (pinfunction "VIN_2") (pintype "power_in"))
      (node (ref "U10") (pin "1") (pinfunction "IN_1") (pintype "passive"))
      (node (ref "U3") (pin "1") (pinfunction "IN_1") (pintype "passive"))
      (node (ref "U4") (pin "1") (pinfunction "IN_1") (pintype "passive"))
      (node (ref "U5") (pin "1") (pinfunction "IN_1") (pintype "passive"))
      (node (ref "U6") (pin "1") (pinfunction "IN_1") (pintype "passive"))
      (node (ref "U7") (pin "1") (pinfunction "IN_1") (pintype "passive"))
      (node (ref "U8") (pin "4") (pinfunction "EN_4") (pintype "power_in"))
      (node (ref "U8") (pin "5") (pinfunction "IN_5") (pintype "power_in"))
    )
    (net (code "7") (name "+24V") (class "Default")
      (node (ref "C26") (pin "1") (pinfunction "1_1") (pintype "passive"))
      (node (ref "D3") (pin "C") (pinfunction "C_C") (pintype "passive"))
      (node (ref "J11") (pin "1") (pinfunction "1_1") (pintype "power_in"))
      (node (ref "R13") (pin "2") (pinfunction "2_2") (pintype "passive"))
      (node (ref "R9") (pin "2") (pinfunction "2_2") (pintype "passive"))
    )
    (net (code "8") (name "/Servo1") (class "Default")
      (node (ref "J3") (pin "1") (pinfunction "1_1") (pintype "passive"))
      (node (ref "P1") (pin "5") (pinfunction "5_5") (pintype "passive"))
    )
    (net (code "9") (name "/Servo2") (class "Default")
      (node (ref "J4") (pin "1") (pinfunction "1_1") (pintype "passive"))
      (node (ref "P1") (pin "4") (pinfunction "4_4") (pintype "passive"))
    )
    (net (code "10") (name "/Servo3") (class "Default")
      (node (ref "J5") (pin "1") (pinfunction "1_1") (pintype "passive"))
      (node (ref "P1") (pin "3") (pinfunction "3_3") (pintype "passive"))
    )
    (net (code "11") (name "/Servo4") (class "Default")
      (node (ref "J6") (pin "1") (pinfunction "1_1") (pintype "passive"))
      (node (ref "P1") (pin "2") (pinfunction "2_2") (pintype "passive"))
    )
    (net (code "12") (name "/Servo5") (class "Default")
      (node (ref "J7") (pin "1") (pinfunction "1_1") (pintype "passive"))
      (node (ref "P1") (pin "1") (pinfunction "1_1") (pintype "passive"))
    )
    (net (code "13") (name "GND") (class "Default")
      (node (ref "C15") (pin "2") (pinfunction "2_2") (pintype "passive"))
      (node (ref "C16") (pin "2") (pinfunction "2_2") (pintype "passive"))
      (node (ref "C17") (pin "2") (pinfunction "2_2") (pintype "passive"))
      (node (ref "C18") (pin "2") (pinfunction "2_2") (pintype "passive"))
      (node (ref "C19") (pin "2") (pinfunction "2_2") (pintype "passive"))
      (node (ref "C2") (pin "2") (pinfunction "2_2") (pintype "passive"))
      (node (ref "C20") (pin "2") (pinfunction "2_2") (pintype "passive"))
      (node (ref "C21") (pin "2") (pinfunction "2_2") (pintype "passive"))
      (node (ref "C22") (pin "2") (pinfunction "2_2") (pintype "passive"))
      (node (ref "C23") (pin "2") (pinfunction "2_2") (pintype "passive"))
      (node (ref "C24") (pin "2") (pinfunction "2_2") (pintype "passive"))
      (node (ref "C25") (pin "2") (pinfunction "2_2") (pintype "passive"))
      (node (ref "C26") (pin "2") (pinfunction "2_2") (pintype "passive"))
      (node (ref "C27") (pin "2") (pinfunction "2_2") (pintype "passive"))
      (node (ref "C28") (pin "2") (pinfunction "2_2") (pintype "passive"))
      (node (ref "C29") (pin "2") (pinfunction "2_2") (pintype "passive"))
      (node (ref "C3") (pin "2") (pinfunction "2_2") (pintype "passive"))
      (node (ref "C30") (pin "2") (pinfunction "2_2") (pintype "passive"))
      (node (ref "C31") (pin "2") (pinfunction "2_2") (pintype "passive"))
      (node (ref "C32") (pin "2") (pinfunction "2_2") (pintype "passive"))
      (node (ref "C33") (pin "2") (pinfunction "2_2") (pintype "passive"))
      (node (ref "C34") (pin "2") (pinfunction "2_2") (pintype "passive"))
      (node (ref "C35") (pin "2") (pinfunction "2_2") (pintype "passive"))
      (node (ref "C4") (pin "2") (pinfunction "2_2") (pintype "passive"))
      (node (ref "C5") (pin "2") (pinfunction "2_2") (pintype "passive"))
      (node (ref "C54") (pin "2") (pinfunction "2_2") (pintype "passive"))
      (node (ref "C55") (pin "2") (pinfunction "2_2") (pintype "passive"))
      (node (ref "C56") (pin "2") (pinfunction "2_2") (pintype "passive"))
      (node (ref "C57") (pin "2") (pinfunction "2_2") (pintype "passive"))
      (node (ref "C6") (pin "2") (pinfunction "2_2") (pintype "passive"))
      (node (ref "C7") (pin "2") (pinfunction "2_2") (pintype "passive"))
      (node (ref "D1") (pin "A") (pinfunction "A_A") (pintype "passive"))
      (node (ref "D12") (pin "2") (pinfunction "2_2") (pintype "passive"))
      (node (ref "D13") (pin "2") (pinfunction "2_2") (pintype "passive"))
      (node (ref "D4") (pin "2") (pinfunction "2_2") (pintype "passive"))
      (node (ref "D5") (pin "2") (pinfunction "2_2") (pintype "passive"))
      (node (ref "D6") (pin "2") (pinfunction "2_2") (pintype "passive"))
      (node (ref "D7") (pin "2") (pinfunction "2_2") (pintype "passive"))
      (node (ref "J1") (pin "4") (pinfunction "GND_4") (pintype "passive"))
      (node (ref "J11") (pin "2") (pinfunction "2_2") (pintype "power_in"))
      (node (ref "J11") (pin "3") (pinfunction "3_3") (pintype "power_in"))
      (node (ref "J12") (pin "2") (pinfunction "2_2") (pintype "power_in"))
      (node (ref "J12") (pin "3") (pinfunction "3_3") (pintype "power_in"))
      (node (ref "J2") (pin "2") (pinfunction "-_2") (pintype "passive"))
      (node (ref "J3") (pin "3") (pinfunction "3_3") (pintype "passive"))
      (node (ref "J4") (pin "3") (pinfunction "3_3") (pintype "passive"))
      (node (ref "J5") (pin "3") (pinfunction "3_3") (pintype "passive"))
      (node (ref "J6") (pin "3") (pinfunction "3_3") (pintype "passive"))
      (node (ref "J7") (pin "3") (pinfunction "3_3") (pintype "passive"))
      (node (ref "J8") (pin "2") (pinfunction "-_2") (pintype "passive"))
      (node (ref "J9") (pin "2") (pinfunction "2_2") (pintype "power_in"))
      (node (ref "J9") (pin "3") (pinfunction "3_3") (pintype "power_in"))
      (node (ref "MH7") (pin "1") (pinfunction "1_1") (pintype "passive"))
      (node (ref "MH8") (pin "1") (pinfunction "1_1") (pintype "passive"))
      (node (ref "P2") (pin "10") (pinfunction "10_10") (pintype "power_in"))
      (node (ref "P2") (pin "6") (pinfunction "6_6") (pintype "power_in"))
      (node (ref "P2") (pin "7") (pinfunction "7_7") (pintype "power_in"))
      (node (ref "P2") (pin "8") (pinfunction "8_8") (pintype "power_in"))
      (node (ref "P2") (pin "9") (pinfunction "9_9") (pintype "power_in"))
      (node (ref "P3") (pin "10") (pinfunction "10_10") (pintype "power_in"))
      (node (ref "P3") (pin "6") (pinfunction "6_6") (pintype "power_in"))
      (node (ref "P3") (pin "7") (pinfunction "7_7") (pintype "power_in"))
      (node (ref "P3") (pin "8") (pinfunction "8_8") (pintype "power_in"))
      (node (ref "P3") (pin "9") (pinfunction "9_9") (pintype "power_in"))
      (node (ref "R10") (pin "1") (pinfunction "1_1") (pintype "passive"))
      (node (ref "R2") (pin "1") (pinfunction "1_1") (pintype "passive"))
      (node (ref "R4") (pin "1") (pinfunction "1_1") (pintype "passive"))
      (node (ref "U1") (pin "11") (pinfunction "TP_11") (pintype "power_in"))
      (node (ref "U1") (pin "8") (pinfunction "GND_8") (pintype "power_in"))
      (node (ref "U10") (pin "2") (pinfunction "GND_2") (pintype "passive"))
      (node (ref "U3") (pin "2") (pinfunction "GND_2") (pintype "passive"))
      (node (ref "U4") (pin "2") (pinfunction "GND_2") (pintype "passive"))
      (node (ref "U5") (pin "2") (pinfunction "GND_2") (pintype "passive"))
      (node (ref "U6") (pin "2") (pinfunction "GND_2") (pintype "passive"))
      (node (ref "U7") (pin "2") (pinfunction "GND_2") (pintype "passive"))
      (node (ref "U8") (pin "2") (pinfunction "GND_2") (pintype "power_in"))
      (node (ref "U9") (pin "1") (pinfunction "GND_1") (pintype "passive"))
    )
    (net (code "14") (name "Net-(C7-Pad1)") (class "Default")
      (node (ref "C7") (pin "1") (pinfunction "1_1") (pintype "passive"))
      (node (ref "R3") (pin "1") (pinfunction "1_1") (pintype "passive"))
    )
    (net (code "15") (name "Net-(D4-Pad1)") (class "Default")
      (node (ref "D4") (pin "1") (pinfunction "1_1") (pintype "passive"))
      (node (ref "R11") (pin "1") (pinfunction "1_1") (pintype "passive"))
    )
    (net (code "16") (name "Net-(D5-Pad1)") (class "Default")
      (node (ref "D5") (pin "1") (pinfunction "1_1") (pintype "passive"))
      (node (ref "R12") (pin "1") (pinfunction "1_1") (pintype "passive"))
    )
    (net (code "17") (name "Net-(D6-Pad1)") (class "Default")
      (node (ref "D6") (pin "1") (pinfunction "1_1") (pintype "passive"))
      (node (ref "R13") (pin "1") (pinfunction "1_1") (pintype "passive"))
    )
    (net (code "18") (name "Net-(D7-Pad1)") (class "Default")
      (node (ref "D7") (pin "1") (pinfunction "1_1") (pintype "passive"))
      (node (ref "R14") (pin "1") (pinfunction "1_1") (pintype "passive"))
    )
    (net (code "19") (name "Net-(D12-Pad1)") (class "Default")
      (node (ref "D12") (pin "1") (pinfunction "1_1") (pintype "passive"))
      (node (ref "R19") (pin "1") (pinfunction "1_1") (pintype "passive"))
    )
    (net (code "20") (name "Net-(D13-Pad1)") (class "Default")
      (node (ref "D13") (pin "1") (pinfunction "1_1") (pintype "passive"))
      (node (ref "R20") (pin "1") (pinfunction "1_1") (pintype "passive"))
    )
    (net (code "21") (name "Net-(U1-BOOT)") (class "Default")
      (node (ref "C1") (pin "1") (pinfunction "1_1") (pintype "passive"))
      (node (ref "U1") (pin "1") (pinfunction "BOOT_1") (pintype "output"))
    )
    (net (code "22") (name "Net-(U1-COMP)") (class "Default")
      (node (ref "C6") (pin "1") (pinfunction "1_1") (pintype "passive"))
      (node (ref "R3") (pin "2") (pinfunction "2_2") (pintype "passive"))
      (node (ref "U1") (pin "7") (pinfunction "COMP_7") (pintype "output"))
    )
    (net (code "23") (name "Net-(U1-FB)") (class "Default")
      (node (ref "R1") (pin "1") (pinfunction "1_1") (pintype "passive"))
      (node (ref "R2") (pin "2") (pinfunction "2_2") (pintype "passive"))
      (node (ref "U1") (pin "6") (pinfunction "FB_6") (pintype "input"))
    )
    (net (code "24") (name "Net-(U1-RT{slash}CLK)") (class "Default")
      (node (ref "R4") (pin "2") (pinfunction "2_2") (pintype "passive"))
      (node (ref "U1") (pin "5") (pinfunction "RT/CLK_5") (pintype "input"))
    )
    (net (code "25") (name "Net-(U1-SS{slash}TR)") (class "Default")
      (node (ref "C5") (pin "1") (pinfunction "1_1") (pintype "passive"))
      (node (ref "U1") (pin "4") (pinfunction "SS/TR_4") (pintype "output"))
    )
    (net (code "26") (name "Net-(U1-SW)") (class "Default")
      (node (ref "C1") (pin "2") (pinfunction "2_2") (pintype "passive"))
      (node (ref "D1") (pin "C") (pinfunction "C_C") (pintype "passive"))
      (node (ref "L1") (pin "2") (pinfunction "2_2") (pintype "passive"))
      (node (ref "U1") (pin "9") (pinfunction "SW_9") (pintype "input"))
    )
    (net (code "27") (name "Net-(U8-FB)") (class "Default")
      (node (ref "R10") (pin "2") (pinfunction "2_2") (pintype "passive"))
      (node (ref "R9") (pin "1") (pinfunction "1_1") (pintype "passive"))
      (node (ref "U8") (pin "3") (pinfunction "FB_3") (pintype "power_in"))
    )
    (net (code "28") (name "Net-(U8-SW)") (class "Default")
      (node (ref "D3") (pin "A") (pinfunction "A_A") (pintype "passive"))
      (node (ref "L3") (pin "1") (pinfunction "1_1") (pintype "passive"))
      (node (ref "U8") (pin "1") (pinfunction "SW_1") (pintype "power_in"))
    )
    (net (code "29") (name "Net-(U9-IN)") (class "Default")
      (node (ref "C27") (pin "1") (pinfunction "1_1") (pintype "passive"))
      (node (ref "C28") (pin "1") (pinfunction "1_1") (pintype "passive"))
      (node (ref "JP1") (pin "2") (pinfunction "2_2") (pintype "passive"))
      (node (ref "U9") (pin "3") (pinfunction "IN_3") (pintype "passive"))
    )
    (net (code "30") (name "unconnected-(J1-D+-Pad3)") (class "Default")
      (node (ref "J1") (pin "3") (pinfunction "D+_3") (pintype "passive"))
    )
    (net (code "31") (name "unconnected-(J1-D--Pad2)") (class "Default")
      (node (ref "J1") (pin "2") (pinfunction "D-_2") (pintype "passive"))
    )
    (net (code "32") (name "unconnected-(MH1-Pad1)") (class "Default")
      (node (ref "MH1") (pin "1") (pinfunction "1_1") (pintype "passive+no_connect"))
    )
    (net (code "33") (name "unconnected-(MH2-Pad1)") (class "Default")
      (node (ref "MH2") (pin "1") (pinfunction "1_1") (pintype "passive+no_connect"))
    )
    (net (code "34") (name "unconnected-(MH3-Pad1)") (class "Default")
      (node (ref "MH3") (pin "1") (pinfunction "1_1") (pintype "passive+no_connect"))
    )
    (net (code "35") (name "unconnected-(MH4-Pad1)") (class "Default")
      (node (ref "MH4") (pin "1") (pinfunction "1_1") (pintype "passive+no_connect"))
    )
    (net (code "36") (name "unconnected-(U1-EN-Pad3)") (class "Default")
      (node (ref "U1") (pin "3") (pinfunction "EN_3") (pintype "input+no_connect"))
    )
    (net (code "37") (name "unconnected-(U1-PWRGD-Pad10)") (class "Default")
      (node (ref "U1") (pin "10") (pinfunction "PWRGD_10") (pintype "output+no_connect"))
    )
    (net (code "38") (name "unconnected-(U8-NC-Pad6)") (class "Default")
      (node (ref "U8") (pin "6") (pinfunction "NC_6") (pintype "passive+no_connect"))
    )
    (net (code "39") (name "unconnected-(U9-OUT-Pad4)") (class "Default")
      (node (ref "U9") (pin "4") (pinfunction "OUT_4") (pintype "passive+no_connect"))
    )
  )
)
